# breakout.net
KiCad netlist of a schematic drawn in Altium Designer
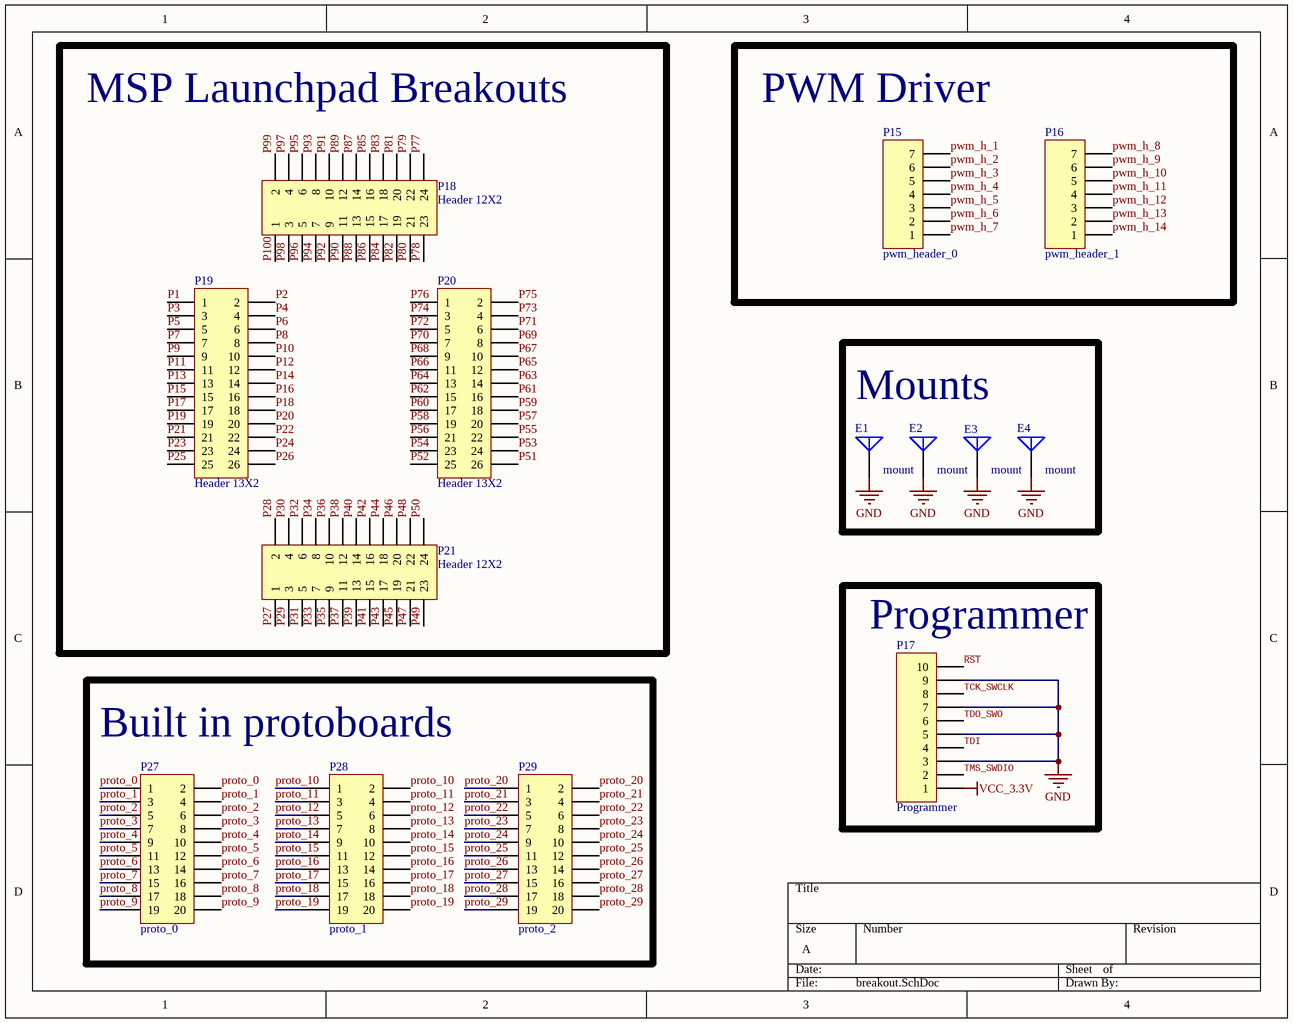
[diagram p0: breakout.SchDoc]

(export (version "E")
  (design (tool "Eeschema 10.0.6"))
  (components
    (comp (ref "E1")
      (value "mount")
      (footprint "PIN1")
      (description "Generic Antenna")
      (fields (field (name "PUBLISHER") "Altium Limited"))
      (libsource (lib "Miscellaneous Devices") (part "Antenna"))
    )
    (comp (ref "E2")
      (value "mount")
      (footprint "PIN1")
      (description "Generic Antenna")
      (fields (field (name "PUBLISHER") "Altium Limited"))
      (libsource (lib "Miscellaneous Devices") (part "Antenna"))
    )
    (comp (ref "E3")
      (value "mount")
      (footprint "PIN1")
      (description "Generic Antenna")
      (fields (field (name "PUBLISHER") "Altium Limited"))
      (libsource (lib "Miscellaneous Devices") (part "Antenna"))
    )
    (comp (ref "E4")
      (value "mount")
      (footprint "PIN1")
      (description "Generic Antenna")
      (fields (field (name "PUBLISHER") "Altium Limited"))
      (libsource (lib "Miscellaneous Devices") (part "Antenna"))
    )
    (comp (ref "P15")
      (value "pwm_header_0")
      (footprint "HDR1X7")
      (description "Header, 7-Pin")
      (fields (field (name "PUBLISHER") "Altium Limited"))
      (libsource (lib "Miscellaneous Connectors") (part "Header 7"))
    )
    (comp (ref "P16")
      (value "pwm_header_1")
      (footprint "HDR1X7")
      (description "Header, 7-Pin")
      (fields (field (name "PUBLISHER") "Altium Limited"))
      (libsource (lib "Miscellaneous Connectors") (part "Header 7"))
    )
    (comp (ref "P17")
      (value "Programmer")
      (footprint "HDR1X10")
      (description "Header, 10-Pin")
      (fields (field (name "PUBLISHER") "Altium Limited"))
      (libsource (lib "Miscellaneous Connectors") (part "Header 10"))
    )
    (comp (ref "P18")
      (value "Header 12X2")
      (footprint "HDR2X12")
      (description "Header, 12-Pin, Dual row")
      (fields (field (name "PUBLISHER") "Altium Limited"))
      (libsource (lib "Miscellaneous Connectors") (part "Header 12X2"))
    )
    (comp (ref "P19")
      (value "Header 13X2")
      (footprint "HDR2X13")
      (description "Header, 13-Pin, Dual row")
      (fields (field (name "PUBLISHER") "Altium Limited"))
      (libsource (lib "Miscellaneous Connectors") (part "Header 13X2"))
    )
    (comp (ref "P20")
      (value "Header 13X2")
      (footprint "HDR2X13")
      (description "Header, 13-Pin, Dual row")
      (fields (field (name "PUBLISHER") "Altium Limited"))
      (libsource (lib "Miscellaneous Connectors") (part "Header 13X2"))
    )
    (comp (ref "P21")
      (value "Header 12X2")
      (footprint "HDR2X12")
      (description "Header, 12-Pin, Dual row")
      (fields (field (name "PUBLISHER") "Altium Limited"))
      (libsource (lib "Miscellaneous Connectors") (part "Header 12X2"))
    )
    (comp (ref "P27")
      (value "proto_0")
      (footprint "HDR2X10")
      (description "Header, 10-Pin, Dual row")
      (fields (field (name "PUBLISHER") "Altium Limited"))
      (libsource (lib "Miscellaneous Connectors") (part "Header 10X2"))
    )
    (comp (ref "P28")
      (value "proto_1")
      (footprint "HDR2X10")
      (description "Header, 10-Pin, Dual row")
      (fields (field (name "PUBLISHER") "Altium Limited"))
      (libsource (lib "Miscellaneous Connectors") (part "Header 10X2"))
    )
    (comp (ref "P29")
      (value "proto_2")
      (footprint "HDR2X10")
      (description "Header, 10-Pin, Dual row")
      (fields (field (name "PUBLISHER") "Altium Limited"))
      (libsource (lib "Miscellaneous Connectors") (part "Header 10X2"))
    )
  )
  (nets
    (net (code "1") (name "/P1") (class "Default")
      (node (ref "P19") (pin "1") (pinfunction "1_1") (pintype "passive"))
    )
    (net (code "2") (name "/P2") (class "Default")
      (node (ref "P19") (pin "2") (pinfunction "2_2") (pintype "passive"))
    )
    (net (code "3") (name "/P3") (class "Default")
      (node (ref "P19") (pin "3") (pinfunction "3_3") (pintype "passive"))
    )
    (net (code "4") (name "/P4") (class "Default")
      (node (ref "P19") (pin "4") (pinfunction "4_4") (pintype "passive"))
    )
    (net (code "5") (name "/P5") (class "Default")
      (node (ref "P19") (pin "5") (pinfunction "5_5") (pintype "passive"))
    )
    (net (code "6") (name "/P6") (class "Default")
      (node (ref "P19") (pin "6") (pinfunction "6_6") (pintype "passive"))
    )
    (net (code "7") (name "/P7") (class "Default")
      (node (ref "P19") (pin "7") (pinfunction "7_7") (pintype "passive"))
    )
    (net (code "8") (name "/P8") (class "Default")
      (node (ref "P19") (pin "8") (pinfunction "8_8") (pintype "passive"))
    )
    (net (code "9") (name "/P9") (class "Default")
      (node (ref "P19") (pin "9") (pinfunction "9_9") (pintype "passive"))
    )
    (net (code "10") (name "/P10") (class "Default")
      (node (ref "P19") (pin "10") (pinfunction "10_10") (pintype "passive"))
    )
    (net (code "11") (name "/P11") (class "Default")
      (node (ref "P19") (pin "11") (pinfunction "11_11") (pintype "passive"))
    )
    (net (code "12") (name "/P12") (class "Default")
      (node (ref "P19") (pin "12") (pinfunction "12_12") (pintype "passive"))
    )
    (net (code "13") (name "/P13") (class "Default")
      (node (ref "P19") (pin "13") (pinfunction "13_13") (pintype "passive"))
    )
    (net (code "14") (name "/P14") (class "Default")
      (node (ref "P19") (pin "14") (pinfunction "14_14") (pintype "passive"))
    )
    (net (code "15") (name "/P15") (class "Default")
      (node (ref "P19") (pin "15") (pinfunction "15_15") (pintype "passive"))
    )
    (net (code "16") (name "/P16") (class "Default")
      (node (ref "P19") (pin "16") (pinfunction "16_16") (pintype "passive"))
    )
    (net (code "17") (name "/P17") (class "Default")
      (node (ref "P19") (pin "17") (pinfunction "17_17") (pintype "passive"))
    )
    (net (code "18") (name "/P18") (class "Default")
      (node (ref "P19") (pin "18") (pinfunction "18_18") (pintype "passive"))
    )
    (net (code "19") (name "/P19") (class "Default")
      (node (ref "P19") (pin "19") (pinfunction "19_19") (pintype "passive"))
    )
    (net (code "20") (name "/P20") (class "Default")
      (node (ref "P19") (pin "20") (pinfunction "20_20") (pintype "passive"))
    )
    (net (code "21") (name "/P21") (class "Default")
      (node (ref "P19") (pin "21") (pinfunction "21_21") (pintype "passive"))
    )
    (net (code "22") (name "/P22") (class "Default")
      (node (ref "P19") (pin "22") (pinfunction "22_22") (pintype "passive"))
    )
    (net (code "23") (name "/P23") (class "Default")
      (node (ref "P19") (pin "23") (pinfunction "23_23") (pintype "passive"))
    )
    (net (code "24") (name "/P24") (class "Default")
      (node (ref "P19") (pin "24") (pinfunction "24_24") (pintype "passive"))
    )
    (net (code "25") (name "/P25") (class "Default")
      (node (ref "P19") (pin "25") (pinfunction "25_25") (pintype "passive"))
    )
    (net (code "26") (name "/P26") (class "Default")
      (node (ref "P19") (pin "26") (pinfunction "26_26") (pintype "passive"))
    )
    (net (code "27") (name "/P27") (class "Default")
      (node (ref "P21") (pin "1") (pinfunction "1_1") (pintype "passive"))
    )
    (net (code "28") (name "/P28") (class "Default")
      (node (ref "P21") (pin "2") (pinfunction "2_2") (pintype "passive"))
    )
    (net (code "29") (name "/P29") (class "Default")
      (node (ref "P21") (pin "3") (pinfunction "3_3") (pintype "passive"))
    )
    (net (code "30") (name "/P30") (class "Default")
      (node (ref "P21") (pin "4") (pinfunction "4_4") (pintype "passive"))
    )
    (net (code "31") (name "/P31") (class "Default")
      (node (ref "P21") (pin "5") (pinfunction "5_5") (pintype "passive"))
    )
    (net (code "32") (name "/P32") (class "Default")
      (node (ref "P21") (pin "6") (pinfunction "6_6") (pintype "passive"))
    )
    (net (code "33") (name "/P33") (class "Default")
      (node (ref "P21") (pin "7") (pinfunction "7_7") (pintype "passive"))
    )
    (net (code "34") (name "/P34") (class "Default")
      (node (ref "P21") (pin "8") (pinfunction "8_8") (pintype "passive"))
    )
    (net (code "35") (name "/P35") (class "Default")
      (node (ref "P21") (pin "9") (pinfunction "9_9") (pintype "passive"))
    )
    (net (code "36") (name "/P36") (class "Default")
      (node (ref "P21") (pin "10") (pinfunction "10_10") (pintype "passive"))
    )
    (net (code "37") (name "/P37") (class "Default")
      (node (ref "P21") (pin "11") (pinfunction "11_11") (pintype "passive"))
    )
    (net (code "38") (name "/P38") (class "Default")
      (node (ref "P21") (pin "12") (pinfunction "12_12") (pintype "passive"))
    )
    (net (code "39") (name "/P39") (class "Default")
      (node (ref "P21") (pin "13") (pinfunction "13_13") (pintype "passive"))
    )
    (net (code "40") (name "/P40") (class "Default")
      (node (ref "P21") (pin "14") (pinfunction "14_14") (pintype "passive"))
    )
    (net (code "41") (name "/P41") (class "Default")
      (node (ref "P21") (pin "15") (pinfunction "15_15") (pintype "passive"))
    )
    (net (code "42") (name "/P42") (class "Default")
      (node (ref "P21") (pin "16") (pinfunction "16_16") (pintype "passive"))
    )
    (net (code "43") (name "/P43") (class "Default")
      (node (ref "P21") (pin "17") (pinfunction "17_17") (pintype "passive"))
    )
    (net (code "44") (name "/P44") (class "Default")
      (node (ref "P21") (pin "18") (pinfunction "18_18") (pintype "passive"))
    )
    (net (code "45") (name "/P45") (class "Default")
      (node (ref "P21") (pin "19") (pinfunction "19_19") (pintype "passive"))
    )
    (net (code "46") (name "/P46") (class "Default")
      (node (ref "P21") (pin "20") (pinfunction "20_20") (pintype "passive"))
    )
    (net (code "47") (name "/P47") (class "Default")
      (node (ref "P21") (pin "21") (pinfunction "21_21") (pintype "passive"))
    )
    (net (code "48") (name "/P48") (class "Default")
      (node (ref "P21") (pin "22") (pinfunction "22_22") (pintype "passive"))
    )
    (net (code "49") (name "/P49") (class "Default")
      (node (ref "P21") (pin "23") (pinfunction "23_23") (pintype "passive"))
    )
    (net (code "50") (name "/P50") (class "Default")
      (node (ref "P21") (pin "24") (pinfunction "24_24") (pintype "passive"))
    )
    (net (code "51") (name "/P51") (class "Default")
      (node (ref "P20") (pin "26") (pinfunction "26_26") (pintype "passive"))
    )
    (net (code "52") (name "/P52") (class "Default")
      (node (ref "P20") (pin "25") (pinfunction "25_25") (pintype "passive"))
    )
    (net (code "53") (name "/P53") (class "Default")
      (node (ref "P20") (pin "24") (pinfunction "24_24") (pintype "passive"))
    )
    (net (code "54") (name "/P54") (class "Default")
      (node (ref "P20") (pin "23") (pinfunction "23_23") (pintype "passive"))
    )
    (net (code "55") (name "/P55") (class "Default")
      (node (ref "P20") (pin "22") (pinfunction "22_22") (pintype "passive"))
    )
    (net (code "56") (name "/P56") (class "Default")
      (node (ref "P20") (pin "21") (pinfunction "21_21") (pintype "passive"))
    )
    (net (code "57") (name "/P57") (class "Default")
      (node (ref "P20") (pin "20") (pinfunction "20_20") (pintype "passive"))
    )
    (net (code "58") (name "/P58") (class "Default")
      (node (ref "P20") (pin "19") (pinfunction "19_19") (pintype "passive"))
    )
    (net (code "59") (name "/P59") (class "Default")
      (node (ref "P20") (pin "18") (pinfunction "18_18") (pintype "passive"))
    )
    (net (code "60") (name "/P60") (class "Default")
      (node (ref "P20") (pin "17") (pinfunction "17_17") (pintype "passive"))
    )
    (net (code "61") (name "/P61") (class "Default")
      (node (ref "P20") (pin "16") (pinfunction "16_16") (pintype "passive"))
    )
    (net (code "62") (name "/P62") (class "Default")
      (node (ref "P20") (pin "15") (pinfunction "15_15") (pintype "passive"))
    )
    (net (code "63") (name "/P63") (class "Default")
      (node (ref "P20") (pin "14") (pinfunction "14_14") (pintype "passive"))
    )
    (net (code "64") (name "/P64") (class "Default")
      (node (ref "P20") (pin "13") (pinfunction "13_13") (pintype "passive"))
    )
    (net (code "65") (name "/P65") (class "Default")
      (node (ref "P20") (pin "12") (pinfunction "12_12") (pintype "passive"))
    )
    (net (code "66") (name "/P66") (class "Default")
      (node (ref "P20") (pin "11") (pinfunction "11_11") (pintype "passive"))
    )
    (net (code "67") (name "/P67") (class "Default")
      (node (ref "P20") (pin "10") (pinfunction "10_10") (pintype "passive"))
    )
    (net (code "68") (name "/P68") (class "Default")
      (node (ref "P20") (pin "9") (pinfunction "9_9") (pintype "passive"))
    )
    (net (code "69") (name "/P69") (class "Default")
      (node (ref "P20") (pin "8") (pinfunction "8_8") (pintype "passive"))
    )
    (net (code "70") (name "/P70") (class "Default")
      (node (ref "P20") (pin "7") (pinfunction "7_7") (pintype "passive"))
    )
    (net (code "71") (name "/P71") (class "Default")
      (node (ref "P20") (pin "6") (pinfunction "6_6") (pintype "passive"))
    )
    (net (code "72") (name "/P72") (class "Default")
      (node (ref "P20") (pin "5") (pinfunction "5_5") (pintype "passive"))
    )
    (net (code "73") (name "/P73") (class "Default")
      (node (ref "P20") (pin "4") (pinfunction "4_4") (pintype "passive"))
    )
    (net (code "74") (name "/P74") (class "Default")
      (node (ref "P20") (pin "3") (pinfunction "3_3") (pintype "passive"))
    )
    (net (code "75") (name "/P75") (class "Default")
      (node (ref "P20") (pin "2") (pinfunction "2_2") (pintype "passive"))
    )
    (net (code "76") (name "/P76") (class "Default")
      (node (ref "P20") (pin "1") (pinfunction "1_1") (pintype "passive"))
    )
    (net (code "77") (name "/P77") (class "Default")
      (node (ref "P18") (pin "24") (pinfunction "24_24") (pintype "passive"))
    )
    (net (code "78") (name "/P78") (class "Default")
      (node (ref "P18") (pin "23") (pinfunction "23_23") (pintype "passive"))
    )
    (net (code "79") (name "/P79") (class "Default")
      (node (ref "P18") (pin "22") (pinfunction "22_22") (pintype "passive"))
    )
    (net (code "80") (name "/P80") (class "Default")
      (node (ref "P18") (pin "21") (pinfunction "21_21") (pintype "passive"))
    )
    (net (code "81") (name "/P81") (class "Default")
      (node (ref "P18") (pin "20") (pinfunction "20_20") (pintype "passive"))
    )
    (net (code "82") (name "/P82") (class "Default")
      (node (ref "P18") (pin "19") (pinfunction "19_19") (pintype "passive"))
    )
    (net (code "83") (name "/P83") (class "Default")
      (node (ref "P18") (pin "18") (pinfunction "18_18") (pintype "passive"))
    )
    (net (code "84") (name "/P84") (class "Default")
      (node (ref "P18") (pin "17") (pinfunction "17_17") (pintype "passive"))
    )
    (net (code "85") (name "/P85") (class "Default")
      (node (ref "P18") (pin "16") (pinfunction "16_16") (pintype "passive"))
    )
    (net (code "86") (name "/P86") (class "Default")
      (node (ref "P18") (pin "15") (pinfunction "15_15") (pintype "passive"))
    )
    (net (code "87") (name "/P87") (class "Default")
      (node (ref "P18") (pin "14") (pinfunction "14_14") (pintype "passive"))
    )
    (net (code "88") (name "/P88") (class "Default")
      (node (ref "P18") (pin "13") (pinfunction "13_13") (pintype "passive"))
    )
    (net (code "89") (name "/P89") (class "Default")
      (node (ref "P18") (pin "12") (pinfunction "12_12") (pintype "passive"))
    )
    (net (code "90") (name "/P90") (class "Default")
      (node (ref "P18") (pin "11") (pinfunction "11_11") (pintype "passive"))
    )
    (net (code "91") (name "/P91") (class "Default")
      (node (ref "P18") (pin "10") (pinfunction "10_10") (pintype "passive"))
    )
    (net (code "92") (name "/P92") (class "Default")
      (node (ref "P18") (pin "9") (pinfunction "9_9") (pintype "passive"))
    )
    (net (code "93") (name "/P93") (class "Default")
      (node (ref "P18") (pin "8") (pinfunction "8_8") (pintype "passive"))
    )
    (net (code "94") (name "/P94") (class "Default")
      (node (ref "P18") (pin "7") (pinfunction "7_7") (pintype "passive"))
    )
    (net (code "95") (name "/P95") (class "Default")
      (node (ref "P18") (pin "6") (pinfunction "6_6") (pintype "passive"))
    )
    (net (code "96") (name "/P96") (class "Default")
      (node (ref "P18") (pin "5") (pinfunction "5_5") (pintype "passive"))
    )
    (net (code "97") (name "/P97") (class "Default")
      (node (ref "P18") (pin "4") (pinfunction "4_4") (pintype "passive"))
    )
    (net (code "98") (name "/P98") (class "Default")
      (node (ref "P18") (pin "3") (pinfunction "3_3") (pintype "passive"))
    )
    (net (code "99") (name "/P99") (class "Default")
      (node (ref "P18") (pin "2") (pinfunction "2_2") (pintype "passive"))
    )
    (net (code "100") (name "/P100") (class "Default")
      (node (ref "P18") (pin "1") (pinfunction "1_1") (pintype "passive"))
    )
    (net (code "101") (name "/TCK_SWCLK") (class "Default")
      (node (ref "P17") (pin "8") (pinfunction "8_8") (pintype "passive"))
    )
    (net (code "102") (name "/TDI") (class "Default")
      (node (ref "P17") (pin "4") (pinfunction "4_4") (pintype "passive"))
    )
    (net (code "103") (name "/TDO_SWO") (class "Default")
      (node (ref "P17") (pin "6") (pinfunction "6_6") (pintype "passive"))
    )
    (net (code "104") (name "/TMS_SWDIO") (class "Default")
      (node (ref "P17") (pin "2") (pinfunction "2_2") (pintype "passive"))
    )
    (net (code "105") (name "/proto_0") (class "Default")
      (node (ref "P27") (pin "1") (pinfunction "1_1") (pintype "passive"))
      (node (ref "P27") (pin "2") (pinfunction "2_2") (pintype "passive"))
    )
    (net (code "106") (name "/proto_1") (class "Default")
      (node (ref "P27") (pin "3") (pinfunction "3_3") (pintype "passive"))
      (node (ref "P27") (pin "4") (pinfunction "4_4") (pintype "passive"))
    )
    (net (code "107") (name "/proto_2") (class "Default")
      (node (ref "P27") (pin "5") (pinfunction "5_5") (pintype "passive"))
      (node (ref "P27") (pin "6") (pinfunction "6_6") (pintype "passive"))
    )
    (net (code "108") (name "/proto_3") (class "Default")
      (node (ref "P27") (pin "7") (pinfunction "7_7") (pintype "passive"))
      (node (ref "P27") (pin "8") (pinfunction "8_8") (pintype "passive"))
    )
    (net (code "109") (name "/proto_4") (class "Default")
      (node (ref "P27") (pin "10") (pinfunction "10_10") (pintype "passive"))
      (node (ref "P27") (pin "9") (pinfunction "9_9") (pintype "passive"))
    )
    (net (code "110") (name "/proto_5") (class "Default")
      (node (ref "P27") (pin "11") (pinfunction "11_11") (pintype "passive"))
      (node (ref "P27") (pin "12") (pinfunction "12_12") (pintype "passive"))
    )
    (net (code "111") (name "/proto_6") (class "Default")
      (node (ref "P27") (pin "13") (pinfunction "13_13") (pintype "passive"))
      (node (ref "P27") (pin "14") (pinfunction "14_14") (pintype "passive"))
    )
    (net (code "112") (name "/proto_7") (class "Default")
      (node (ref "P27") (pin "15") (pinfunction "15_15") (pintype "passive"))
      (node (ref "P27") (pin "16") (pinfunction "16_16") (pintype "passive"))
    )
    (net (code "113") (name "/proto_8") (class "Default")
      (node (ref "P27") (pin "17") (pinfunction "17_17") (pintype "passive"))
      (node (ref "P27") (pin "18") (pinfunction "18_18") (pintype "passive"))
    )
    (net (code "114") (name "/proto_9") (class "Default")
      (node (ref "P27") (pin "19") (pinfunction "19_19") (pintype "passive"))
      (node (ref "P27") (pin "20") (pinfunction "20_20") (pintype "passive"))
    )
    (net (code "115") (name "/proto_10") (class "Default")
      (node (ref "P28") (pin "1") (pinfunction "1_1") (pintype "passive"))
      (node (ref "P28") (pin "2") (pinfunction "2_2") (pintype "passive"))
    )
    (net (code "116") (name "/proto_11") (class "Default")
      (node (ref "P28") (pin "3") (pinfunction "3_3") (pintype "passive"))
      (node (ref "P28") (pin "4") (pinfunction "4_4") (pintype "passive"))
    )
    (net (code "117") (name "/proto_12") (class "Default")
      (node (ref "P28") (pin "5") (pinfunction "5_5") (pintype "passive"))
      (node (ref "P28") (pin "6") (pinfunction "6_6") (pintype "passive"))
    )
    (net (code "118") (name "/proto_13") (class "Default")
      (node (ref "P28") (pin "7") (pinfunction "7_7") (pintype "passive"))
      (node (ref "P28") (pin "8") (pinfunction "8_8") (pintype "passive"))
    )
    (net (code "119") (name "/proto_14") (class "Default")
      (node (ref "P28") (pin "10") (pinfunction "10_10") (pintype "passive"))
      (node (ref "P28") (pin "9") (pinfunction "9_9") (pintype "passive"))
    )
    (net (code "120") (name "/proto_15") (class "Default")
      (node (ref "P28") (pin "11") (pinfunction "11_11") (pintype "passive"))
      (node (ref "P28") (pin "12") (pinfunction "12_12") (pintype "passive"))
    )
    (net (code "121") (name "/proto_16") (class "Default")
      (node (ref "P28") (pin "13") (pinfunction "13_13") (pintype "passive"))
      (node (ref "P28") (pin "14") (pinfunction "14_14") (pintype "passive"))
    )
    (net (code "122") (name "/proto_17") (class "Default")
      (node (ref "P28") (pin "15") (pinfunction "15_15") (pintype "passive"))
      (node (ref "P28") (pin "16") (pinfunction "16_16") (pintype "passive"))
    )
    (net (code "123") (name "/proto_18") (class "Default")
      (node (ref "P28") (pin "17") (pinfunction "17_17") (pintype "passive"))
      (node (ref "P28") (pin "18") (pinfunction "18_18") (pintype "passive"))
    )
    (net (code "124") (name "/proto_19") (class "Default")
      (node (ref "P28") (pin "19") (pinfunction "19_19") (pintype "passive"))
      (node (ref "P28") (pin "20") (pinfunction "20_20") (pintype "passive"))
    )
    (net (code "125") (name "/proto_20") (class "Default")
      (node (ref "P29") (pin "1") (pinfunction "1_1") (pintype "passive"))
      (node (ref "P29") (pin "2") (pinfunction "2_2") (pintype "passive"))
    )
    (net (code "126") (name "/proto_21") (class "Default")
      (node (ref "P29") (pin "3") (pinfunction "3_3") (pintype "passive"))
      (node (ref "P29") (pin "4") (pinfunction "4_4") (pintype "passive"))
    )
    (net (code "127") (name "/proto_22") (class "Default")
      (node (ref "P29") (pin "5") (pinfunction "5_5") (pintype "passive"))
      (node (ref "P29") (pin "6") (pinfunction "6_6") (pintype "passive"))
    )
    (net (code "128") (name "/proto_23") (class "Default")
      (node (ref "P29") (pin "7") (pinfunction "7_7") (pintype "passive"))
      (node (ref "P29") (pin "8") (pinfunction "8_8") (pintype "passive"))
    )
    (net (code "129") (name "/proto_24") (class "Default")
      (node (ref "P29") (pin "10") (pinfunction "10_10") (pintype "passive"))
      (node (ref "P29") (pin "9") (pinfunction "9_9") (pintype "passive"))
    )
    (net (code "130") (name "/proto_25") (class "Default")
      (node (ref "P29") (pin "11") (pinfunction "11_11") (pintype "passive"))
      (node (ref "P29") (pin "12") (pinfunction "12_12") (pintype "passive"))
    )
    (net (code "131") (name "/proto_26") (class "Default")
      (node (ref "P29") (pin "13") (pinfunction "13_13") (pintype "passive"))
      (node (ref "P29") (pin "14") (pinfunction "14_14") (pintype "passive"))
    )
    (net (code "132") (name "/proto_27") (class "Default")
      (node (ref "P29") (pin "15") (pinfunction "15_15") (pintype "passive"))
      (node (ref "P29") (pin "16") (pinfunction "16_16") (pintype "passive"))
    )
    (net (code "133") (name "/proto_28") (class "Default")
      (node (ref "P29") (pin "17") (pinfunction "17_17") (pintype "passive"))
      (node (ref "P29") (pin "18") (pinfunction "18_18") (pintype "passive"))
    )
    (net (code "134") (name "/proto_29") (class "Default")
      (node (ref "P29") (pin "19") (pinfunction "19_19") (pintype "passive"))
      (node (ref "P29") (pin "20") (pinfunction "20_20") (pintype "passive"))
    )
    (net (code "135") (name "/pwm_h_1") (class "Default")
      (node (ref "P15") (pin "7") (pinfunction "7_7") (pintype "passive"))
    )
    (net (code "136") (name "/pwm_h_2") (class "Default")
      (node (ref "P15") (pin "6") (pinfunction "6_6") (pintype "passive"))
    )
    (net (code "137") (name "/pwm_h_3") (class "Default")
      (node (ref "P15") (pin "5") (pinfunction "5_5") (pintype "passive"))
    )
    (net (code "138") (name "/pwm_h_4") (class "Default")
      (node (ref "P15") (pin "4") (pinfunction "4_4") (pintype "passive"))
    )
    (net (code "139") (name "/pwm_h_5") (class "Default")
      (node (ref "P15") (pin "3") (pinfunction "3_3") (pintype "passive"))
    )
    (net (code "140") (name "/pwm_h_6") (class "Default")
      (node (ref "P15") (pin "2") (pinfunction "2_2") (pintype "passive"))
    )
    (net (code "141") (name "/pwm_h_7") (class "Default")
      (node (ref "P15") (pin "1") (pinfunction "1_1") (pintype "passive"))
    )
    (net (code "142") (name "/pwm_h_8") (class "Default")
      (node (ref "P16") (pin "7") (pinfunction "7_7") (pintype "passive"))
    )
    (net (code "143") (name "/pwm_h_9") (class "Default")
      (node (ref "P16") (pin "6") (pinfunction "6_6") (pintype "passive"))
    )
    (net (code "144") (name "/pwm_h_10") (class "Default")
      (node (ref "P16") (pin "5") (pinfunction "5_5") (pintype "passive"))
    )
    (net (code "145") (name "/pwm_h_11") (class "Default")
      (node (ref "P16") (pin "4") (pinfunction "4_4") (pintype "passive"))
    )
    (net (code "146") (name "/pwm_h_12") (class "Default")
      (node (ref "P16") (pin "3") (pinfunction "3_3") (pintype "passive"))
    )
    (net (code "147") (name "/pwm_h_13") (class "Default")
      (node (ref "P16") (pin "2") (pinfunction "2_2") (pintype "passive"))
    )
    (net (code "148") (name "/pwm_h_14") (class "Default")
      (node (ref "P16") (pin "1") (pinfunction "1_1") (pintype "passive"))
    )
    (net (code "149") (name "/~{RST}") (class "Default")
      (node (ref "P17") (pin "10") (pinfunction "10_10") (pintype "passive"))
    )
    (net (code "150") (name "GND") (class "Default")
      (node (ref "E1") (pin "1") (pinfunction "A_1") (pintype "passive"))
      (node (ref "E2") (pin "1") (pinfunction "A_1") (pintype "passive"))
      (node (ref "E3") (pin "1") (pinfunction "A_1") (pintype "passive"))
      (node (ref "E4") (pin "1") (pinfunction "A_1") (pintype "passive"))
      (node (ref "P17") (pin "3") (pinfunction "3_3") (pintype "passive"))
      (node (ref "P17") (pin "5") (pinfunction "5_5") (pintype "passive"))
      (node (ref "P17") (pin "7") (pinfunction "7_7") (pintype "passive"))
      (node (ref "P17") (pin "9") (pinfunction "9_9") (pintype "passive"))
    )
    (net (code "151") (name "VCC_3.3V") (class "Default")
      (node (ref "P17") (pin "1") (pinfunction "1_1") (pintype "passive"))
    )
  )
)
